# schematic-thermometer.net
KiCad netlist of a schematic drawn in EasyEDA
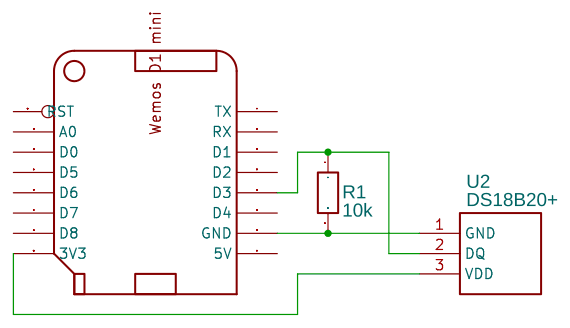
[diagram p0: schematic sheet]

(export (version "E")
  (design (tool "Eeschema 10.0.6"))
  (components
    (comp (ref "R1") (value "10k") (libsource (lib "") (part "Res_AXIAL-0.3(1/8W)_EU")))
    (comp (ref "U1")
      (value "WEMOS_D1_mini")
      (fields
        (field (name "BOM_Manufacturer Part") "WeMos D1 Mini Pro")
        (field (name "BOM_Supplier Part") "undefined")
      )
      (libsource (lib "") (part "Unknown_100_70"))
    )
    (comp (ref "U2")
      (value "DS18B20+")
      (fields (field (name "BOM_Supplier Part") "C9753"))
      (libsource (lib "") (part "Unknown_270_110"))
    )
  )
  (nets
    (net (code "1") (name "Net-(U2-DQ)") (class "Default")
      (node (ref "R1") (pin "1") (pinfunction "1_1") (pintype "unspecified"))
      (node (ref "U1") (pin "D3") (pinfunction "D3_D3") (pintype "unspecified"))
      (node (ref "U2") (pin "2") (pinfunction "DQ_2") (pintype "unspecified"))
    )
    (net (code "2") (name "Net-(U2-GND)") (class "Default")
      (node (ref "R1") (pin "2") (pinfunction "2_2") (pintype "unspecified"))
      (node (ref "U1") (pin "GND") (pinfunction "GND_GND") (pintype "unspecified"))
      (node (ref "U2") (pin "1") (pinfunction "GND_1") (pintype "unspecified"))
    )
    (net (code "3") (name "Net-(U2-VDD)") (class "Default")
      (node (ref "U1") (pin "3V3") (pinfunction "3V3_3V3") (pintype "unspecified"))
      (node (ref "U2") (pin "3") (pinfunction "VDD_3") (pintype "unspecified"))
    )
    (net (code "4") (name "unconnected-(U1-Pad5V)") (class "Default")
      (node (ref "U1") (pin "5V") (pinfunction "5V_5V") (pintype "unspecified"))
    )
    (net (code "5") (name "unconnected-(U1-PadA0)") (class "Default")
      (node (ref "U1") (pin "A0") (pinfunction "A0_A0") (pintype "unspecified"))
    )
    (net (code "6") (name "unconnected-(U1-PadD0)") (class "Default")
      (node (ref "U1") (pin "D0") (pinfunction "D0_D0") (pintype "unspecified"))
    )
    (net (code "7") (name "unconnected-(U1-PadD1)") (class "Default")
      (node (ref "U1") (pin "D1") (pinfunction "D1_D1") (pintype "unspecified"))
    )
    (net (code "8") (name "unconnected-(U1-PadD2)") (class "Default")
      (node (ref "U1") (pin "D2") (pinfunction "D2_D2") (pintype "unspecified"))
    )
    (net (code "9") (name "unconnected-(U1-PadD4)") (class "Default")
      (node (ref "U1") (pin "D4") (pinfunction "D4_D4") (pintype "unspecified"))
    )
    (net (code "10") (name "unconnected-(U1-PadD5)") (class "Default")
      (node (ref "U1") (pin "D5") (pinfunction "D5_D5") (pintype "unspecified"))
    )
    (net (code "11") (name "unconnected-(U1-PadD6)") (class "Default")
      (node (ref "U1") (pin "D6") (pinfunction "D6_D6") (pintype "unspecified"))
    )
    (net (code "12") (name "unconnected-(U1-PadD7)") (class "Default")
      (node (ref "U1") (pin "D7") (pinfunction "D7_D7") (pintype "unspecified"))
    )
    (net (code "13") (name "unconnected-(U1-PadD8)") (class "Default")
      (node (ref "U1") (pin "D8") (pinfunction "D8_D8") (pintype "unspecified"))
    )
    (net (code "14") (name "unconnected-(U1-PadRST)") (class "Default")
      (node (ref "U1") (pin "RST") (pinfunction "RST_RST") (pintype "unspecified"))
    )
    (net (code "15") (name "unconnected-(U1-PadRX)") (class "Default")
      (node (ref "U1") (pin "RX") (pinfunction "RX_RX") (pintype "unspecified"))
    )
    (net (code "16") (name "unconnected-(U1-PadTX)") (class "Default")
      (node (ref "U1") (pin "TX") (pinfunction "TX_TX") (pintype "unspecified"))
    )
  )
)
